# connect.net
KiCad netlist of a schematic drawn in Altium Designer
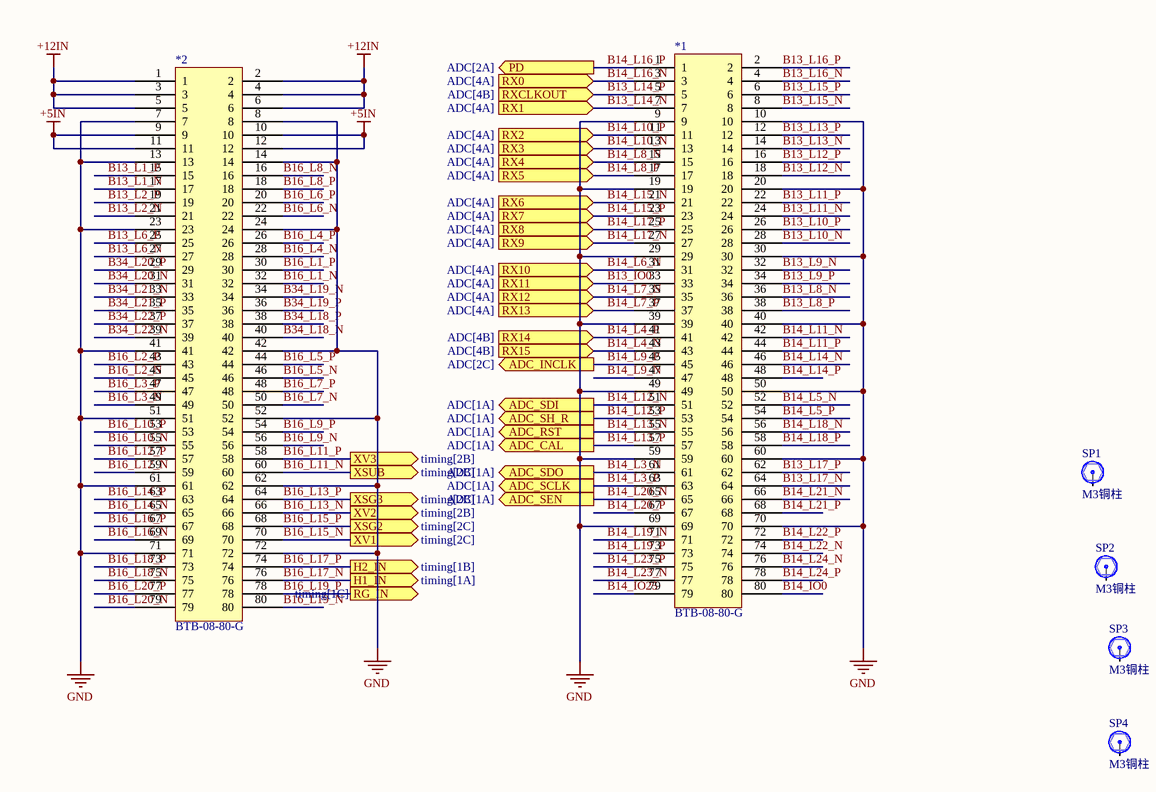
[diagram p0: connect.SchDoc]

(export (version "E")
  (design (tool "Eeschema 10.0.6"))
  (components
    (comp (ref "*1")
      (value "BTB-08-80-G")
      (footprint "BTB-08-80-G")
      (libsource (lib "0.04连接器") (part "BTB-08-80-G"))
    )
    (comp (ref "*2")
      (value "BTB-08-80-G")
      (footprint "BTB-08-80-G")
      (libsource (lib "0.04连接器") (part "BTB-08-80-G"))
    )
    (comp (ref "SP1")
      (value "M3铜柱")
      (footprint "M3x5_N")
      (description "铜柱")
      (fields (field (name "版权归属") "封装库来自淘宝 ID：黄晶宝石"))
      (libsource (lib "9.09-固定柱") (part "铜柱大焊盘"))
    )
    (comp (ref "SP2")
      (value "M3铜柱")
      (footprint "M3x5_N")
      (description "铜柱")
      (fields (field (name "版权归属") "封装库来自淘宝 ID：黄晶宝石"))
      (libsource (lib "9.09-固定柱") (part "铜柱大焊盘"))
    )
    (comp (ref "SP3")
      (value "M3铜柱")
      (footprint "M3x5_N")
      (description "铜柱")
      (fields (field (name "版权归属") "封装库来自淘宝 ID：黄晶宝石"))
      (libsource (lib "9.09-固定柱") (part "铜柱大焊盘"))
    )
    (comp (ref "SP4")
      (value "M3铜柱")
      (footprint "M3x5_N")
      (description "铜柱")
      (fields (field (name "版权归属") "封装库来自淘宝 ID：黄晶宝石"))
      (libsource (lib "9.09-固定柱") (part "铜柱大焊盘"))
    )
  )
  (nets
    (net (code "1") (name "+5IN") (class "Default")
      (node (ref "*2") (pin "10") (pinfunction "10_10") (pintype "passive"))
      (node (ref "*2") (pin "11") (pinfunction "11_11") (pintype "passive"))
      (node (ref "*2") (pin "12") (pinfunction "12_12") (pintype "passive"))
      (node (ref "*2") (pin "9") (pinfunction "9_9") (pintype "passive"))
    )
    (net (code "2") (name "+12IN") (class "Default")
      (node (ref "*2") (pin "1") (pinfunction "1_1") (pintype "passive"))
      (node (ref "*2") (pin "2") (pinfunction "2_2") (pintype "passive"))
      (node (ref "*2") (pin "3") (pinfunction "3_3") (pintype "passive"))
      (node (ref "*2") (pin "4") (pinfunction "4_4") (pintype "passive"))
      (node (ref "*2") (pin "5") (pinfunction "5_5") (pintype "passive"))
      (node (ref "*2") (pin "6") (pinfunction "6_6") (pintype "passive"))
    )
    (net (code "3") (name "/B13_IO0") (class "Default")
      (node (ref "*1") (pin "33") (pinfunction "33_33") (pintype "passive"))
    )
    (net (code "4") (name "/B13_L1_N") (class "Default")
      (node (ref "*2") (pin "17") (pinfunction "17_17") (pintype "passive"))
    )
    (net (code "5") (name "/B13_L1_P") (class "Default")
      (node (ref "*2") (pin "15") (pinfunction "15_15") (pintype "passive"))
    )
    (net (code "6") (name "/B13_L2_N") (class "Default")
      (node (ref "*2") (pin "21") (pinfunction "21_21") (pintype "passive"))
    )
    (net (code "7") (name "/B13_L2_P") (class "Default")
      (node (ref "*2") (pin "19") (pinfunction "19_19") (pintype "passive"))
    )
    (net (code "8") (name "/B13_L6_N") (class "Default")
      (node (ref "*2") (pin "27") (pinfunction "27_27") (pintype "passive"))
    )
    (net (code "9") (name "/B13_L6_P") (class "Default")
      (node (ref "*2") (pin "25") (pinfunction "25_25") (pintype "passive"))
    )
    (net (code "10") (name "/B13_L8_N") (class "Default")
      (node (ref "*1") (pin "36") (pinfunction "36_36") (pintype "passive"))
    )
    (net (code "11") (name "/B13_L8_P") (class "Default")
      (node (ref "*1") (pin "38") (pinfunction "38_38") (pintype "passive"))
    )
    (net (code "12") (name "/B13_L9_N") (class "Default")
      (node (ref "*1") (pin "32") (pinfunction "32_32") (pintype "passive"))
    )
    (net (code "13") (name "/B13_L9_P") (class "Default")
      (node (ref "*1") (pin "34") (pinfunction "34_34") (pintype "passive"))
    )
    (net (code "14") (name "/B13_L10_N") (class "Default")
      (node (ref "*1") (pin "28") (pinfunction "28_28") (pintype "passive"))
    )
    (net (code "15") (name "/B13_L10_P") (class "Default")
      (node (ref "*1") (pin "26") (pinfunction "26_26") (pintype "passive"))
    )
    (net (code "16") (name "/B13_L11_N") (class "Default")
      (node (ref "*1") (pin "24") (pinfunction "24_24") (pintype "passive"))
    )
    (net (code "17") (name "/B13_L11_P") (class "Default")
      (node (ref "*1") (pin "22") (pinfunction "22_22") (pintype "passive"))
    )
    (net (code "18") (name "/B13_L12_N") (class "Default")
      (node (ref "*1") (pin "18") (pinfunction "18_18") (pintype "passive"))
    )
    (net (code "19") (name "/B13_L12_P") (class "Default")
      (node (ref "*1") (pin "16") (pinfunction "16_16") (pintype "passive"))
    )
    (net (code "20") (name "/B13_L13_N") (class "Default")
      (node (ref "*1") (pin "14") (pinfunction "14_14") (pintype "passive"))
    )
    (net (code "21") (name "/B13_L13_P") (class "Default")
      (node (ref "*1") (pin "12") (pinfunction "12_12") (pintype "passive"))
    )
    (net (code "22") (name "/B13_L14_N") (class "Default")
      (node (ref "*1") (pin "7") (pinfunction "7_7") (pintype "passive"))
    )
    (net (code "23") (name "/B13_L14_P") (class "Default")
      (node (ref "*1") (pin "5") (pinfunction "5_5") (pintype "passive"))
    )
    (net (code "24") (name "/B13_L15_N") (class "Default")
      (node (ref "*1") (pin "8") (pinfunction "8_8") (pintype "passive"))
    )
    (net (code "25") (name "/B13_L15_P") (class "Default")
      (node (ref "*1") (pin "6") (pinfunction "6_6") (pintype "passive"))
    )
    (net (code "26") (name "/B13_L16_N") (class "Default")
      (node (ref "*1") (pin "4") (pinfunction "4_4") (pintype "passive"))
    )
    (net (code "27") (name "/B13_L16_P") (class "Default")
      (node (ref "*1") (pin "2") (pinfunction "2_2") (pintype "passive"))
    )
    (net (code "28") (name "/B13_L17_N") (class "Default")
      (node (ref "*1") (pin "64") (pinfunction "64_64") (pintype "passive"))
    )
    (net (code "29") (name "/B13_L17_P") (class "Default")
      (node (ref "*1") (pin "62") (pinfunction "62_62") (pintype "passive"))
    )
    (net (code "30") (name "/B14_IO0") (class "Default")
      (node (ref "*1") (pin "80") (pinfunction "80_80") (pintype "passive"))
    )
    (net (code "31") (name "/B14_IO25") (class "Default")
      (node (ref "*1") (pin "79") (pinfunction "79_79") (pintype "passive"))
    )
    (net (code "32") (name "/B14_L3_N") (class "Default")
      (node (ref "*1") (pin "61") (pinfunction "61_61") (pintype "passive"))
    )
    (net (code "33") (name "/B14_L3_P") (class "Default")
      (node (ref "*1") (pin "63") (pinfunction "63_63") (pintype "passive"))
    )
    (net (code "34") (name "/B14_L4_N") (class "Default")
      (node (ref "*1") (pin "43") (pinfunction "43_43") (pintype "passive"))
    )
    (net (code "35") (name "/B14_L4_P") (class "Default")
      (node (ref "*1") (pin "41") (pinfunction "41_41") (pintype "passive"))
    )
    (net (code "36") (name "/B14_L5_N") (class "Default")
      (node (ref "*1") (pin "52") (pinfunction "52_52") (pintype "passive"))
    )
    (net (code "37") (name "/B14_L5_P") (class "Default")
      (node (ref "*1") (pin "54") (pinfunction "54_54") (pintype "passive"))
    )
    (net (code "38") (name "/B14_L6_N") (class "Default")
      (node (ref "*1") (pin "31") (pinfunction "31_31") (pintype "passive"))
    )
    (net (code "39") (name "/B14_L7_N") (class "Default")
      (node (ref "*1") (pin "35") (pinfunction "35_35") (pintype "passive"))
    )
    (net (code "40") (name "/B14_L7_P") (class "Default")
      (node (ref "*1") (pin "37") (pinfunction "37_37") (pintype "passive"))
    )
    (net (code "41") (name "/B14_L8_N") (class "Default")
      (node (ref "*1") (pin "15") (pinfunction "15_15") (pintype "passive"))
    )
    (net (code "42") (name "/B14_L8_P") (class "Default")
      (node (ref "*1") (pin "17") (pinfunction "17_17") (pintype "passive"))
    )
    (net (code "43") (name "/B14_L9_N") (class "Default")
      (node (ref "*1") (pin "47") (pinfunction "47_47") (pintype "passive"))
    )
    (net (code "44") (name "/B14_L9_P") (class "Default")
      (node (ref "*1") (pin "45") (pinfunction "45_45") (pintype "passive"))
    )
    (net (code "45") (name "/B14_L10_N") (class "Default")
      (node (ref "*1") (pin "13") (pinfunction "13_13") (pintype "passive"))
    )
    (net (code "46") (name "/B14_L10_P") (class "Default")
      (node (ref "*1") (pin "11") (pinfunction "11_11") (pintype "passive"))
    )
    (net (code "47") (name "/B14_L11_N") (class "Default")
      (node (ref "*1") (pin "42") (pinfunction "42_42") (pintype "passive"))
    )
    (net (code "48") (name "/B14_L11_P") (class "Default")
      (node (ref "*1") (pin "44") (pinfunction "44_44") (pintype "passive"))
    )
    (net (code "49") (name "/B14_L12_N") (class "Default")
      (node (ref "*1") (pin "51") (pinfunction "51_51") (pintype "passive"))
    )
    (net (code "50") (name "/B14_L12_P") (class "Default")
      (node (ref "*1") (pin "53") (pinfunction "53_53") (pintype "passive"))
    )
    (net (code "51") (name "/B14_L13_N") (class "Default")
      (node (ref "*1") (pin "55") (pinfunction "55_55") (pintype "passive"))
    )
    (net (code "52") (name "/B14_L13_P") (class "Default")
      (node (ref "*1") (pin "57") (pinfunction "57_57") (pintype "passive"))
    )
    (net (code "53") (name "/B14_L14_N") (class "Default")
      (node (ref "*1") (pin "46") (pinfunction "46_46") (pintype "passive"))
    )
    (net (code "54") (name "/B14_L14_P") (class "Default")
      (node (ref "*1") (pin "48") (pinfunction "48_48") (pintype "passive"))
    )
    (net (code "55") (name "/B14_L15_N") (class "Default")
      (node (ref "*1") (pin "21") (pinfunction "21_21") (pintype "passive"))
    )
    (net (code "56") (name "/B14_L15_P") (class "Default")
      (node (ref "*1") (pin "23") (pinfunction "23_23") (pintype "passive"))
    )
    (net (code "57") (name "/B14_L16_N") (class "Default")
      (node (ref "*1") (pin "3") (pinfunction "3_3") (pintype "passive"))
    )
    (net (code "58") (name "/B14_L16_P") (class "Default")
      (node (ref "*1") (pin "1") (pinfunction "1_1") (pintype "passive"))
    )
    (net (code "59") (name "/B14_L17_N") (class "Default")
      (node (ref "*1") (pin "27") (pinfunction "27_27") (pintype "passive"))
    )
    (net (code "60") (name "/B14_L17_P") (class "Default")
      (node (ref "*1") (pin "25") (pinfunction "25_25") (pintype "passive"))
    )
    (net (code "61") (name "/B14_L18_N") (class "Default")
      (node (ref "*1") (pin "56") (pinfunction "56_56") (pintype "passive"))
    )
    (net (code "62") (name "/B14_L18_P") (class "Default")
      (node (ref "*1") (pin "58") (pinfunction "58_58") (pintype "passive"))
    )
    (net (code "63") (name "/B14_L19_N") (class "Default")
      (node (ref "*1") (pin "71") (pinfunction "71_71") (pintype "passive"))
    )
    (net (code "64") (name "/B14_L19_P") (class "Default")
      (node (ref "*1") (pin "73") (pinfunction "73_73") (pintype "passive"))
    )
    (net (code "65") (name "/B14_L20_N") (class "Default")
      (node (ref "*1") (pin "65") (pinfunction "65_65") (pintype "passive"))
    )
    (net (code "66") (name "/B14_L20_P") (class "Default")
      (node (ref "*1") (pin "67") (pinfunction "67_67") (pintype "passive"))
    )
    (net (code "67") (name "/B14_L21_N") (class "Default")
      (node (ref "*1") (pin "66") (pinfunction "66_66") (pintype "passive"))
    )
    (net (code "68") (name "/B14_L21_P") (class "Default")
      (node (ref "*1") (pin "68") (pinfunction "68_68") (pintype "passive"))
    )
    (net (code "69") (name "/B14_L22_N") (class "Default")
      (node (ref "*1") (pin "74") (pinfunction "74_74") (pintype "passive"))
    )
    (net (code "70") (name "/B14_L22_P") (class "Default")
      (node (ref "*1") (pin "72") (pinfunction "72_72") (pintype "passive"))
    )
    (net (code "71") (name "/B14_L23_N") (class "Default")
      (node (ref "*1") (pin "77") (pinfunction "77_77") (pintype "passive"))
    )
    (net (code "72") (name "/B14_L23_P") (class "Default")
      (node (ref "*1") (pin "75") (pinfunction "75_75") (pintype "passive"))
    )
    (net (code "73") (name "/B14_L24_N") (class "Default")
      (node (ref "*1") (pin "76") (pinfunction "76_76") (pintype "passive"))
    )
    (net (code "74") (name "/B14_L24_P") (class "Default")
      (node (ref "*1") (pin "78") (pinfunction "78_78") (pintype "passive"))
    )
    (net (code "75") (name "/B16_L1_N") (class "Default")
      (node (ref "*2") (pin "32") (pinfunction "32_32") (pintype "passive"))
    )
    (net (code "76") (name "/B16_L1_P") (class "Default")
      (node (ref "*2") (pin "30") (pinfunction "30_30") (pintype "passive"))
    )
    (net (code "77") (name "/B16_L2_N") (class "Default")
      (node (ref "*2") (pin "45") (pinfunction "45_45") (pintype "passive"))
    )
    (net (code "78") (name "/B16_L2_P") (class "Default")
      (node (ref "*2") (pin "43") (pinfunction "43_43") (pintype "passive"))
    )
    (net (code "79") (name "/B16_L3_N") (class "Default")
      (node (ref "*2") (pin "49") (pinfunction "49_49") (pintype "passive"))
    )
    (net (code "80") (name "/B16_L3_P") (class "Default")
      (node (ref "*2") (pin "47") (pinfunction "47_47") (pintype "passive"))
    )
    (net (code "81") (name "/B16_L4_N") (class "Default")
      (node (ref "*2") (pin "28") (pinfunction "28_28") (pintype "passive"))
    )
    (net (code "82") (name "/B16_L4_P") (class "Default")
      (node (ref "*2") (pin "26") (pinfunction "26_26") (pintype "passive"))
    )
    (net (code "83") (name "/B16_L5_N") (class "Default")
      (node (ref "*2") (pin "46") (pinfunction "46_46") (pintype "passive"))
    )
    (net (code "84") (name "/B16_L5_P") (class "Default")
      (node (ref "*2") (pin "44") (pinfunction "44_44") (pintype "passive"))
    )
    (net (code "85") (name "/B16_L6_N") (class "Default")
      (node (ref "*2") (pin "22") (pinfunction "22_22") (pintype "passive"))
    )
    (net (code "86") (name "/B16_L6_P") (class "Default")
      (node (ref "*2") (pin "20") (pinfunction "20_20") (pintype "passive"))
    )
    (net (code "87") (name "/B16_L7_N") (class "Default")
      (node (ref "*2") (pin "50") (pinfunction "50_50") (pintype "passive"))
    )
    (net (code "88") (name "/B16_L7_P") (class "Default")
      (node (ref "*2") (pin "48") (pinfunction "48_48") (pintype "passive"))
    )
    (net (code "89") (name "/B16_L8_N") (class "Default")
      (node (ref "*2") (pin "16") (pinfunction "16_16") (pintype "passive"))
    )
    (net (code "90") (name "/B16_L8_P") (class "Default")
      (node (ref "*2") (pin "18") (pinfunction "18_18") (pintype "passive"))
    )
    (net (code "91") (name "/B16_L9_N") (class "Default")
      (node (ref "*2") (pin "56") (pinfunction "56_56") (pintype "passive"))
    )
    (net (code "92") (name "/B16_L9_P") (class "Default")
      (node (ref "*2") (pin "54") (pinfunction "54_54") (pintype "passive"))
    )
    (net (code "93") (name "/B16_L10_N") (class "Default")
      (node (ref "*2") (pin "55") (pinfunction "55_55") (pintype "passive"))
    )
    (net (code "94") (name "/B16_L10_P") (class "Default")
      (node (ref "*2") (pin "53") (pinfunction "53_53") (pintype "passive"))
    )
    (net (code "95") (name "/B16_L11_N") (class "Default")
      (node (ref "*2") (pin "60") (pinfunction "60_60") (pintype "passive"))
    )
    (net (code "96") (name "/B16_L11_P") (class "Default")
      (node (ref "*2") (pin "58") (pinfunction "58_58") (pintype "passive"))
    )
    (net (code "97") (name "/B16_L12_N") (class "Default")
      (node (ref "*2") (pin "59") (pinfunction "59_59") (pintype "passive"))
    )
    (net (code "98") (name "/B16_L12_P") (class "Default")
      (node (ref "*2") (pin "57") (pinfunction "57_57") (pintype "passive"))
    )
    (net (code "99") (name "/B16_L13_N") (class "Default")
      (node (ref "*2") (pin "66") (pinfunction "66_66") (pintype "passive"))
    )
    (net (code "100") (name "/B16_L13_P") (class "Default")
      (node (ref "*2") (pin "64") (pinfunction "64_64") (pintype "passive"))
    )
    (net (code "101") (name "/B16_L14_N") (class "Default")
      (node (ref "*2") (pin "65") (pinfunction "65_65") (pintype "passive"))
    )
    (net (code "102") (name "/B16_L14_P") (class "Default")
      (node (ref "*2") (pin "63") (pinfunction "63_63") (pintype "passive"))
    )
    (net (code "103") (name "/B16_L15_N") (class "Default")
      (node (ref "*2") (pin "70") (pinfunction "70_70") (pintype "passive"))
    )
    (net (code "104") (name "/B16_L15_P") (class "Default")
      (node (ref "*2") (pin "68") (pinfunction "68_68") (pintype "passive"))
    )
    (net (code "105") (name "/B16_L16_N") (class "Default")
      (node (ref "*2") (pin "69") (pinfunction "69_69") (pintype "passive"))
    )
    (net (code "106") (name "/B16_L16_P") (class "Default")
      (node (ref "*2") (pin "67") (pinfunction "67_67") (pintype "passive"))
    )
    (net (code "107") (name "/B16_L17_N") (class "Default")
      (node (ref "*2") (pin "76") (pinfunction "76_76") (pintype "passive"))
    )
    (net (code "108") (name "/B16_L17_P") (class "Default")
      (node (ref "*2") (pin "74") (pinfunction "74_74") (pintype "passive"))
    )
    (net (code "109") (name "/B16_L18_N") (class "Default")
      (node (ref "*2") (pin "75") (pinfunction "75_75") (pintype "passive"))
    )
    (net (code "110") (name "/B16_L18_P") (class "Default")
      (node (ref "*2") (pin "73") (pinfunction "73_73") (pintype "passive"))
    )
    (net (code "111") (name "/B16_L19_N") (class "Default")
      (node (ref "*2") (pin "80") (pinfunction "80_80") (pintype "passive"))
    )
    (net (code "112") (name "/B16_L19_P") (class "Default")
      (node (ref "*2") (pin "78") (pinfunction "78_78") (pintype "passive"))
    )
    (net (code "113") (name "/B16_L20_N") (class "Default")
      (node (ref "*2") (pin "79") (pinfunction "79_79") (pintype "passive"))
    )
    (net (code "114") (name "/B16_L20_P") (class "Default")
      (node (ref "*2") (pin "77") (pinfunction "77_77") (pintype "passive"))
    )
    (net (code "115") (name "/B34_L18_N") (class "Default")
      (node (ref "*2") (pin "40") (pinfunction "40_40") (pintype "passive"))
    )
    (net (code "116") (name "/B34_L18_P") (class "Default")
      (node (ref "*2") (pin "38") (pinfunction "38_38") (pintype "passive"))
    )
    (net (code "117") (name "/B34_L19_N") (class "Default")
      (node (ref "*2") (pin "34") (pinfunction "34_34") (pintype "passive"))
    )
    (net (code "118") (name "/B34_L19_P") (class "Default")
      (node (ref "*2") (pin "36") (pinfunction "36_36") (pintype "passive"))
    )
    (net (code "119") (name "/B34_L20_N") (class "Default")
      (node (ref "*2") (pin "31") (pinfunction "31_31") (pintype "passive"))
    )
    (net (code "120") (name "/B34_L20_P") (class "Default")
      (node (ref "*2") (pin "29") (pinfunction "29_29") (pintype "passive"))
    )
    (net (code "121") (name "/B34_L21_N") (class "Default")
      (node (ref "*2") (pin "33") (pinfunction "33_33") (pintype "passive"))
    )
    (net (code "122") (name "/B34_L21_P") (class "Default")
      (node (ref "*2") (pin "35") (pinfunction "35_35") (pintype "passive"))
    )
    (net (code "123") (name "/B34_L22_N") (class "Default")
      (node (ref "*2") (pin "39") (pinfunction "39_39") (pintype "passive"))
    )
    (net (code "124") (name "/B34_L22_P") (class "Default")
      (node (ref "*2") (pin "37") (pinfunction "37_37") (pintype "passive"))
    )
    (net (code "125") (name "GND") (class "Default")
      (node (ref "*1") (pin "10") (pinfunction "10_10") (pintype "passive"))
      (node (ref "*1") (pin "19") (pinfunction "19_19") (pintype "passive"))
      (node (ref "*1") (pin "20") (pinfunction "20_20") (pintype "passive"))
      (node (ref "*1") (pin "29") (pinfunction "29_29") (pintype "passive"))
      (node (ref "*1") (pin "30") (pinfunction "30_30") (pintype "passive"))
      (node (ref "*1") (pin "39") (pinfunction "39_39") (pintype "passive"))
      (node (ref "*1") (pin "40") (pinfunction "40_40") (pintype "passive"))
      (node (ref "*1") (pin "49") (pinfunction "49_49") (pintype "passive"))
      (node (ref "*1") (pin "50") (pinfunction "50_50") (pintype "passive"))
      (node (ref "*1") (pin "59") (pinfunction "59_59") (pintype "passive"))
      (node (ref "*1") (pin "60") (pinfunction "60_60") (pintype "passive"))
      (node (ref "*1") (pin "69") (pinfunction "69_69") (pintype "passive"))
      (node (ref "*1") (pin "70") (pinfunction "70_70") (pintype "passive"))
      (node (ref "*1") (pin "9") (pinfunction "9_9") (pintype "passive"))
      (node (ref "*2") (pin "13") (pinfunction "13_13") (pintype "passive"))
      (node (ref "*2") (pin "14") (pinfunction "14_14") (pintype "passive"))
      (node (ref "*2") (pin "23") (pinfunction "23_23") (pintype "passive"))
      (node (ref "*2") (pin "24") (pinfunction "24_24") (pintype "passive"))
      (node (ref "*2") (pin "41") (pinfunction "41_41") (pintype "passive"))
      (node (ref "*2") (pin "42") (pinfunction "42_42") (pintype "passive"))
      (node (ref "*2") (pin "51") (pinfunction "51_51") (pintype "passive"))
      (node (ref "*2") (pin "52") (pinfunction "52_52") (pintype "passive"))
      (node (ref "*2") (pin "61") (pinfunction "61_61") (pintype "passive"))
      (node (ref "*2") (pin "62") (pinfunction "62_62") (pintype "passive"))
      (node (ref "*2") (pin "7") (pinfunction "7_7") (pintype "passive"))
      (node (ref "*2") (pin "71") (pinfunction "71_71") (pintype "passive"))
      (node (ref "*2") (pin "72") (pinfunction "72_72") (pintype "passive"))
      (node (ref "*2") (pin "8") (pinfunction "8_8") (pintype "passive"))
    )
    (net (code "126") (name "unconnected-(SP1-Pad1)") (class "Default")
      (node (ref "SP1") (pin "1") (pinfunction "1_1") (pintype "passive"))
    )
    (net (code "127") (name "unconnected-(SP2-Pad1)") (class "Default")
      (node (ref "SP2") (pin "1") (pinfunction "1_1") (pintype "passive"))
    )
    (net (code "128") (name "unconnected-(SP3-Pad1)") (class "Default")
      (node (ref "SP3") (pin "1") (pinfunction "1_1") (pintype "passive"))
    )
    (net (code "129") (name "unconnected-(SP4-Pad1)") (class "Default")
      (node (ref "SP4") (pin "1") (pinfunction "1_1") (pintype "passive"))
    )
  )
)
